# v1_1.net
KiCad netlist of a schematic drawn in Altium Designer
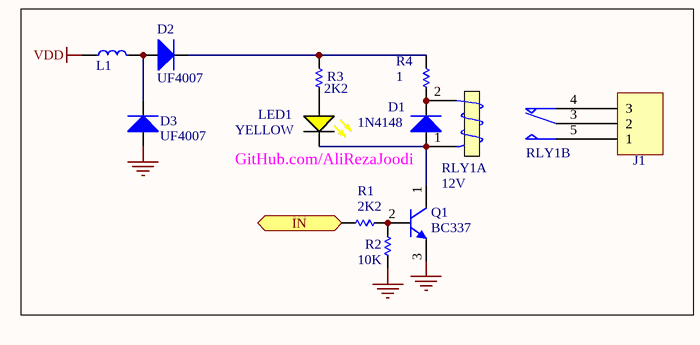
[diagram p0: v1.1.SchDoc]

(export (version "E")
  (design (tool "Eeschema 10.0.6"))
  (components
    (comp (ref "D1")
      (value "1N4148")
      (footprint "DIODE0.4_Glass")
      (description "Default Diode")
      (fields (field (name "MANUFACTURER") "Generic Components") (field (name "PUBLISHER") "Altium Limited"))
      (libsource (lib "Miscellaneous Devices") (part "Diode"))
    )
    (comp (ref "D2")
      (value "UF4007")
      (footprint "D_THD_AXIAL0.4_DO-41")
      (description "Diode,")
      (libsource (lib "Passive") (part "Diode"))
    )
    (comp (ref "D3")
      (value "UF4007")
      (footprint "D_THD_AXIAL0.4_DO-41")
      (description "Diode,")
      (libsource (lib "Passive") (part "Diode"))
    )
    (comp (ref "J1")
      (value "3PIN")
      (footprint "Fonics_3PIN_1")
      (description "Header, 3-Pin")
      (fields (field (name "MANUFACTURER") "Generic Components") (field (name "PUBLISHER") "Altium Limited"))
      (libsource (lib "Miscellaneous Connectors") (part "Header 3"))
    )
    (comp (ref "L1")
      (value "~")
      (description "Inductor,")
      (libsource (lib "Passive") (part "Inductor_2Type"))
    )
    (comp (ref "LED1")
      (value "YELLOW")
      (footprint "LED_THD_3MM_YELLOW_R")
      (description "LED, Yellow")
      (fields (field (name "MANUFACTURER") "Generic Components") (field (name "PUBLISHER") "Altium Limited"))
      (libsource (lib "Display") (part "LED_YELLOW"))
    )
    (comp (ref "Q1")
      (value "BC337")
      (footprint "TO92C")
      (description "NPN Bipolar Transistor")
      (fields (field (name "MANUFACTURER") "Generic Components") (field (name "PUBLISHER") "Altium Limited"))
      (libsource (lib "Miscellaneous Devices") (part "NPN"))
    )
    (comp (ref "R1")
      (value "2K2")
      (footprint "R_THD_AXIAL0.4(1/4W)")
      (description "Resistor")
      (libsource (lib "Passive") (part "Resistor"))
    )
    (comp (ref "R2")
      (value "10K")
      (footprint "R_THD_AXIAL0.4(1/4W)")
      (description "Resistor")
      (libsource (lib "Passive") (part "Resistor"))
    )
    (comp (ref "R3")
      (value "2K2")
      (footprint "R_THD_AXIAL0.4(1/4W)")
      (description "Resistor")
      (libsource (lib "Passive") (part "Resistor"))
    )
    (comp (ref "R4")
      (value "1")
      (footprint "R_THD_AXIAL0.4(1/4W)")
      (description "Resistor")
      (libsource (lib "Passive") (part "Resistor"))
    )
    (comp (ref "RLY1")
      (value "12V")
      (footprint "RELAY_SPDT_5PIN_2216")
      (description "SPDT Relay")
      (libsource (lib "Passive") (part "Relay_SPDT_2Form"))
    )
  )
  (nets
    (net (code "1") (name "/IN") (class "Default")
      (node (ref "R1") (pin "2") (pinfunction "2_2") (pintype "passive"))
    )
    (net (code "2") (name "GND") (class "Default")
      (node (ref "D3") (pin "1") (pinfunction "A_1") (pintype "passive"))
      (node (ref "Q1") (pin "3") (pinfunction "E_3") (pintype "passive"))
      (node (ref "R2") (pin "1") (pinfunction "1_1") (pintype "passive"))
    )
    (net (code "3") (name "Net-(D1-A)") (class "Default")
      (node (ref "D1") (pin "1") (pinfunction "A_1") (pintype "passive"))
      (node (ref "LED1") (pin "2") (pinfunction "K_2") (pintype "passive"))
      (node (ref "Q1") (pin "1") (pinfunction "C_1") (pintype "passive"))
      (node (ref "RLY1") (pin "1") (pinfunction "T2_1") (pintype "passive"))
    )
    (net (code "4") (name "Net-(D1-K)") (class "Default")
      (node (ref "D1") (pin "2") (pinfunction "K_2") (pintype "passive"))
      (node (ref "R4") (pin "1") (pinfunction "1_1") (pintype "passive"))
      (node (ref "RLY1") (pin "2") (pinfunction "T1_2") (pintype "passive"))
    )
    (net (code "5") (name "Net-(D2-A)") (class "Default")
      (node (ref "D2") (pin "1") (pinfunction "A_1") (pintype "passive"))
      (node (ref "D3") (pin "2") (pinfunction "K_2") (pintype "passive"))
      (node (ref "L1") (pin "2") (pinfunction "2_2") (pintype "passive"))
    )
    (net (code "6") (name "Net-(D2-K)") (class "Default")
      (node (ref "D2") (pin "2") (pinfunction "K_2") (pintype "passive"))
      (node (ref "R3") (pin "2") (pinfunction "2_2") (pintype "passive"))
      (node (ref "R4") (pin "2") (pinfunction "2_2") (pintype "passive"))
    )
    (net (code "7") (name "Net-(LED1-A)") (class "Default")
      (node (ref "LED1") (pin "1") (pinfunction "A_1") (pintype "passive"))
      (node (ref "R3") (pin "1") (pinfunction "1_1") (pintype "passive"))
    )
    (net (code "8") (name "Net-(Q1-B)") (class "Default")
      (node (ref "Q1") (pin "2") (pinfunction "B_2") (pintype "passive"))
      (node (ref "R1") (pin "1") (pinfunction "1_1") (pintype "passive"))
      (node (ref "R2") (pin "2") (pinfunction "2_2") (pintype "passive"))
    )
    (net (code "9") (name "Net-(RLY1B-COM)") (class "Default")
      (node (ref "J1") (pin "2") (pinfunction "2_2") (pintype "passive"))
      (node (ref "RLY1") (pin "3") (pinfunction "COM_3") (pintype "passive"))
    )
    (net (code "10") (name "Net-(RLY1B-NC)") (class "Default")
      (node (ref "J1") (pin "3") (pinfunction "3_3") (pintype "passive"))
      (node (ref "RLY1") (pin "4") (pinfunction "NC_4") (pintype "passive"))
    )
    (net (code "11") (name "Net-(RLY1B-NO)") (class "Default")
      (node (ref "J1") (pin "1") (pinfunction "1_1") (pintype "passive"))
      (node (ref "RLY1") (pin "5") (pinfunction "NO_5") (pintype "passive"))
    )
    (net (code "12") (name "VDD") (class "Default")
      (node (ref "L1") (pin "1") (pinfunction "1_1") (pintype "passive"))
    )
  )
)
